# amp_test_filter_route_2.net
KiCad netlist of a schematic drawn in EAGLE
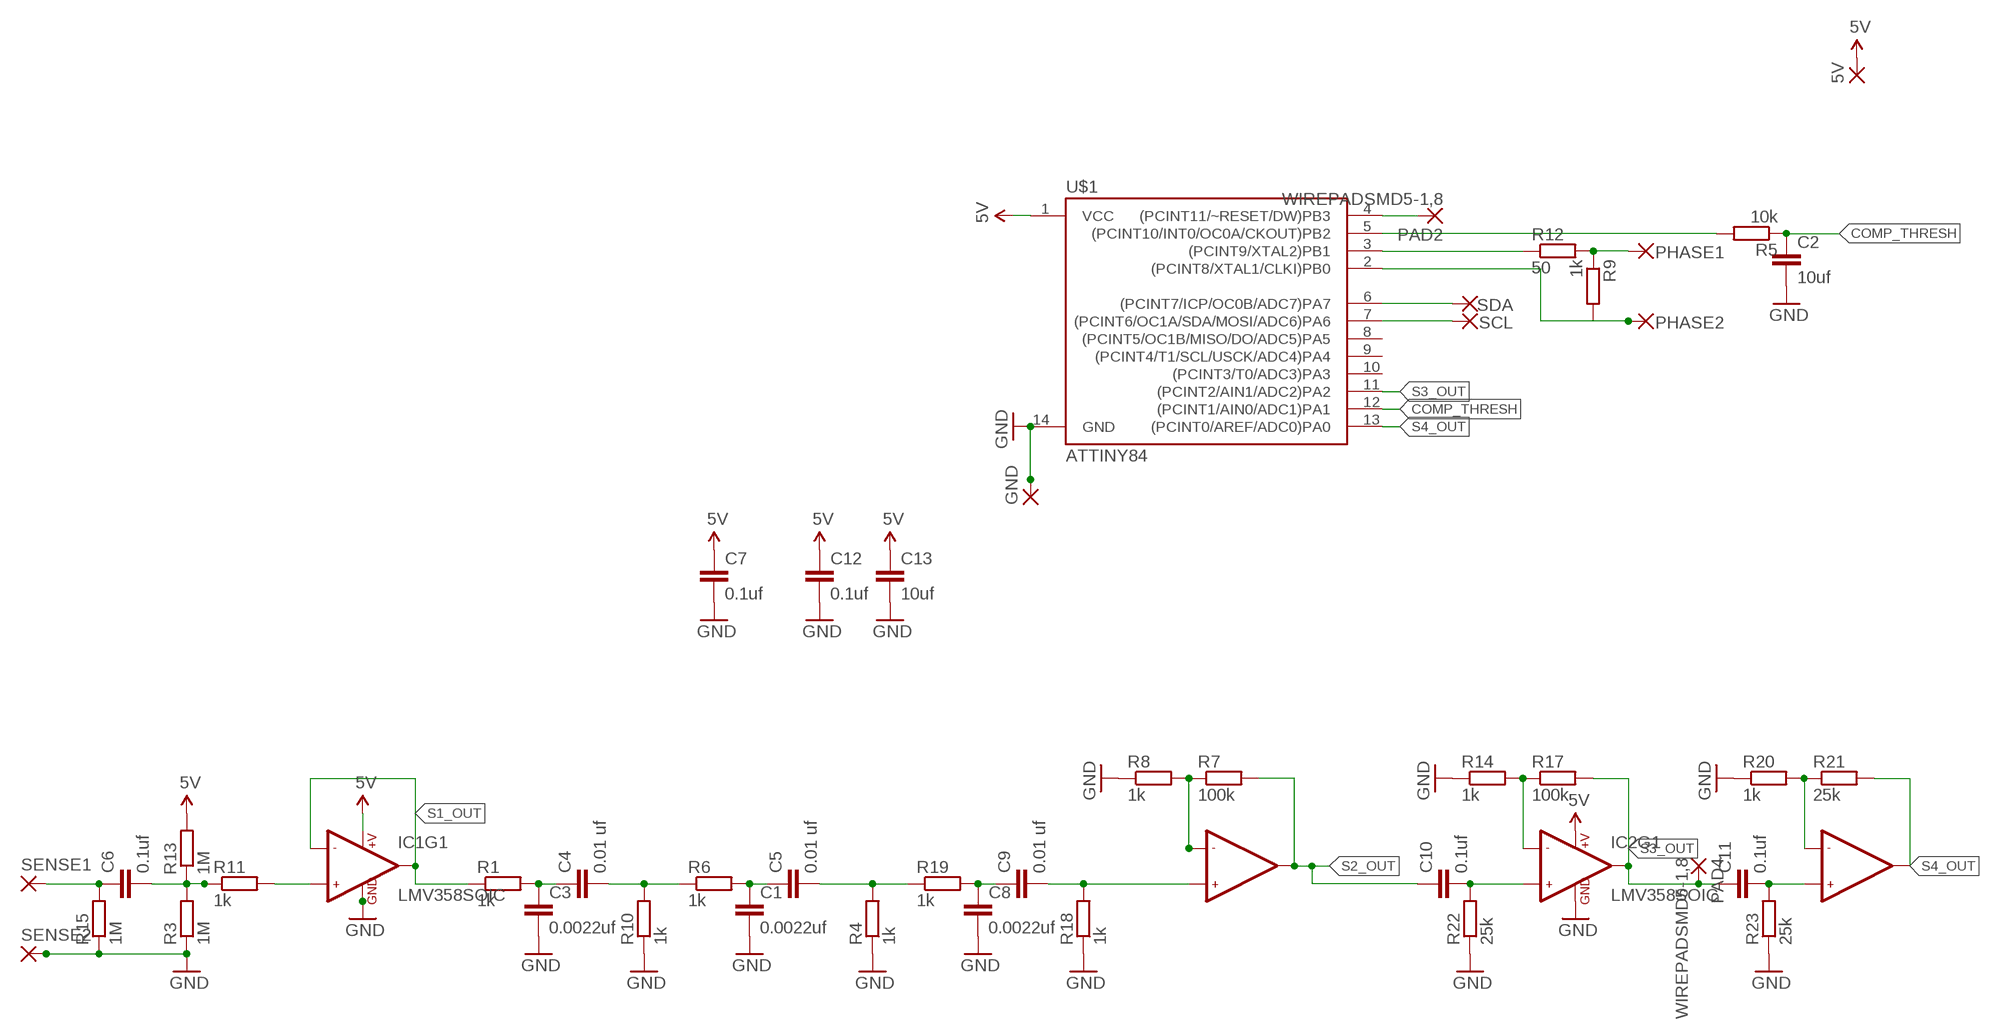
[diagram p0: schematic, sheet 1]

(export (version "E")
  (design (tool "Eeschema 10.0.6"))
  (components
    (comp (ref "5V")
      (value "SMD5")
      (footprint "eagle-import:SMD2,54-5,08")
      (libsource (lib "eagle-import") (part "SMD5"))
    )
    (comp (ref "C1")
      (value "0.0022uf")
      (footprint "eagle-import:C0603")
      (libsource (lib "eagle-import") (part "C-EUC0603"))
    )
    (comp (ref "C2")
      (value "10uf")
      (footprint "eagle-import:C0603")
      (libsource (lib "eagle-import") (part "C-EUC0603"))
    )
    (comp (ref "C3")
      (value "0.0022uf")
      (footprint "eagle-import:C0603")
      (libsource (lib "eagle-import") (part "C-EUC0603"))
    )
    (comp (ref "C4")
      (value "0.01 uf")
      (footprint "eagle-import:C0603")
      (libsource (lib "eagle-import") (part "C-EUC0603"))
    )
    (comp (ref "C5")
      (value "0.01 uf")
      (footprint "eagle-import:C0603")
      (libsource (lib "eagle-import") (part "C-EUC0603"))
    )
    (comp (ref "C6")
      (value "0.1uf")
      (footprint "eagle-import:C0603")
      (libsource (lib "eagle-import") (part "C-EUC0603"))
    )
    (comp (ref "C7")
      (value "0.1uf")
      (footprint "eagle-import:C0603")
      (libsource (lib "eagle-import") (part "C-EUC0603"))
    )
    (comp (ref "C8")
      (value "0.0022uf")
      (footprint "eagle-import:C0603")
      (libsource (lib "eagle-import") (part "C-EUC0603"))
    )
    (comp (ref "C9")
      (value "0.01 uf")
      (footprint "eagle-import:C0603")
      (libsource (lib "eagle-import") (part "C-EUC0603"))
    )
    (comp (ref "C10")
      (value "0.1uf")
      (footprint "eagle-import:C0603")
      (libsource (lib "eagle-import") (part "C-EUC0603"))
    )
    (comp (ref "C11")
      (value "0.1uf")
      (footprint "eagle-import:C0603")
      (libsource (lib "eagle-import") (part "C-EUC0603"))
    )
    (comp (ref "C12")
      (value "0.1uf")
      (footprint "eagle-import:C0603")
      (libsource (lib "eagle-import") (part "C-EUC0603"))
    )
    (comp (ref "C13")
      (value "10uf")
      (footprint "eagle-import:C0603")
      (libsource (lib "eagle-import") (part "C-EUC0603"))
    )
    (comp (ref "GND")
      (value "SMD5")
      (footprint "eagle-import:SMD2,54-5,08")
      (libsource (lib "eagle-import") (part "SMD5"))
    )
    (comp (ref "IC1")
      (value "LMV358SOIC")
      (footprint "eagle-import:SO08")
      (libsource (lib "eagle-import") (part "LMV358SOIC"))
    )
    (comp (ref "IC2")
      (value "LMV358SOIC")
      (footprint "eagle-import:SO08")
      (libsource (lib "eagle-import") (part "LMV358SOIC"))
    )
    (comp (ref "PAD2")
      (value "WIREPADSMD5-1,8")
      (footprint "eagle-import:5-1,8")
      (libsource (lib "eagle-import") (part "WIREPADSMD5-1,8"))
    )
    (comp (ref "PAD4")
      (value "WIREPADSMD5-1,8")
      (footprint "eagle-import:5-1,8")
      (libsource (lib "eagle-import") (part "WIREPADSMD5-1,8"))
    )
    (comp (ref "PHASE1")
      (value "SMD5")
      (footprint "eagle-import:SMD2,54-5,08")
      (libsource (lib "eagle-import") (part "SMD5"))
    )
    (comp (ref "PHASE2")
      (value "SMD5")
      (footprint "eagle-import:SMD2,54-5,08")
      (libsource (lib "eagle-import") (part "SMD5"))
    )
    (comp (ref "R1")
      (value "1k")
      (footprint "eagle-import:R0603")
      (libsource (lib "eagle-import") (part "R-EU_R0603"))
    )
    (comp (ref "R3")
      (value "1M")
      (footprint "eagle-import:R0603")
      (libsource (lib "eagle-import") (part "R-EU_R0603"))
    )
    (comp (ref "R4")
      (value "1k")
      (footprint "eagle-import:R0603")
      (libsource (lib "eagle-import") (part "R-EU_R0603"))
    )
    (comp (ref "R5")
      (value "10k")
      (footprint "eagle-import:R0603")
      (libsource (lib "eagle-import") (part "R-EU_R0603"))
    )
    (comp (ref "R6")
      (value "1k")
      (footprint "eagle-import:R0603")
      (libsource (lib "eagle-import") (part "R-EU_R0603"))
    )
    (comp (ref "R7")
      (value "100k")
      (footprint "eagle-import:R0603")
      (libsource (lib "eagle-import") (part "R-EU_R0603"))
    )
    (comp (ref "R8")
      (value "1k")
      (footprint "eagle-import:R0603")
      (libsource (lib "eagle-import") (part "R-EU_R0603"))
    )
    (comp (ref "R9")
      (value "1k")
      (footprint "eagle-import:R0603")
      (libsource (lib "eagle-import") (part "R-EU_R0603"))
    )
    (comp (ref "R10")
      (value "1k")
      (footprint "eagle-import:R0603")
      (libsource (lib "eagle-import") (part "R-EU_R0603"))
    )
    (comp (ref "R11")
      (value "1k")
      (footprint "eagle-import:R0603")
      (libsource (lib "eagle-import") (part "R-EU_R0603"))
    )
    (comp (ref "R12")
      (value "50")
      (footprint "eagle-import:R0603")
      (libsource (lib "eagle-import") (part "R-EU_R0603"))
    )
    (comp (ref "R13")
      (value "1M")
      (footprint "eagle-import:R0603")
      (libsource (lib "eagle-import") (part "R-EU_R0603"))
    )
    (comp (ref "R14")
      (value "1k")
      (footprint "eagle-import:R0603")
      (libsource (lib "eagle-import") (part "R-EU_R0603"))
    )
    (comp (ref "R15")
      (value "1M")
      (footprint "eagle-import:R0603")
      (libsource (lib "eagle-import") (part "R-EU_R0603"))
    )
    (comp (ref "R17")
      (value "100k")
      (footprint "eagle-import:R0603")
      (libsource (lib "eagle-import") (part "R-EU_R0603"))
    )
    (comp (ref "R18")
      (value "1k")
      (footprint "eagle-import:R0603")
      (libsource (lib "eagle-import") (part "R-EU_R0603"))
    )
    (comp (ref "R19")
      (value "1k")
      (footprint "eagle-import:R0603")
      (libsource (lib "eagle-import") (part "R-EU_R0603"))
    )
    (comp (ref "R20")
      (value "1k")
      (footprint "eagle-import:R0603")
      (libsource (lib "eagle-import") (part "R-EU_R0603"))
    )
    (comp (ref "R21")
      (value "25k")
      (footprint "eagle-import:R0603")
      (libsource (lib "eagle-import") (part "R-EU_R0603"))
    )
    (comp (ref "R22")
      (value "25k")
      (footprint "eagle-import:R0603")
      (libsource (lib "eagle-import") (part "R-EU_R0603"))
    )
    (comp (ref "R23")
      (value "25k")
      (footprint "eagle-import:R0603")
      (libsource (lib "eagle-import") (part "R-EU_R0603"))
    )
    (comp (ref "SCL")
      (value "SMD5")
      (footprint "eagle-import:SMD2,54-5,08")
      (libsource (lib "eagle-import") (part "SMD5"))
    )
    (comp (ref "SDA")
      (value "SMD5")
      (footprint "eagle-import:SMD2,54-5,08")
      (libsource (lib "eagle-import") (part "SMD5"))
    )
    (comp (ref "SENSE1")
      (value "SMD5")
      (footprint "eagle-import:SMD2,54-5,08")
      (libsource (lib "eagle-import") (part "SMD5"))
    )
    (comp (ref "SENSE2")
      (value "SMD5")
      (footprint "eagle-import:SMD2,54-5,08")
      (libsource (lib "eagle-import") (part "SMD5"))
    )
    (comp (ref "U$1")
      (value "ATTINY84")
      (footprint "eagle-import:SO14")
      (libsource (lib "eagle-import") (part "ATTINY84"))
    )
  )
  (nets
    (net (code "1") (name "5V") (class "Default")
      (node (ref "5V") (pin "1") (pinfunction "P_1") (pintype "passive"))
      (node (ref "C12") (pin "1") (pinfunction "1_1") (pintype "passive"))
      (node (ref "C13") (pin "1") (pinfunction "1_1") (pintype "passive"))
      (node (ref "C7") (pin "1") (pinfunction "1_1") (pintype "passive"))
      (node (ref "IC1") (pin "8") (pinfunction "+V_8") (pintype "power_in"))
      (node (ref "IC2") (pin "8") (pinfunction "+V_8") (pintype "power_in"))
      (node (ref "R13") (pin "2") (pinfunction "2_2") (pintype "passive"))
      (node (ref "U$1") (pin "1") (pinfunction "VCC_1") (pintype "bidirectional"))
    )
    (net (code "2") (name "COMP_THRESH") (class "Default")
      (node (ref "C2") (pin "1") (pinfunction "1_1") (pintype "passive"))
      (node (ref "R5") (pin "1") (pinfunction "1_1") (pintype "passive"))
      (node (ref "U$1") (pin "12") (pinfunction "(PCINT1/AIN0/ADC1)PA1_12") (pintype "bidirectional"))
    )
    (net (code "3") (name "GND") (class "Default")
      (node (ref "C1") (pin "2") (pinfunction "2_2") (pintype "passive"))
      (node (ref "C12") (pin "2") (pinfunction "2_2") (pintype "passive"))
      (node (ref "C13") (pin "2") (pinfunction "2_2") (pintype "passive"))
      (node (ref "C2") (pin "2") (pinfunction "2_2") (pintype "passive"))
      (node (ref "C3") (pin "2") (pinfunction "2_2") (pintype "passive"))
      (node (ref "C7") (pin "2") (pinfunction "2_2") (pintype "passive"))
      (node (ref "C8") (pin "2") (pinfunction "2_2") (pintype "passive"))
      (node (ref "GND") (pin "1") (pinfunction "P_1") (pintype "passive"))
      (node (ref "IC1") (pin "4") (pinfunction "GND_4") (pintype "power_in"))
      (node (ref "IC2") (pin "4") (pinfunction "GND_4") (pintype "power_in"))
      (node (ref "R10") (pin "1") (pinfunction "1_1") (pintype "passive"))
      (node (ref "R14") (pin "1") (pinfunction "1_1") (pintype "passive"))
      (node (ref "R15") (pin "1") (pinfunction "1_1") (pintype "passive"))
      (node (ref "R18") (pin "1") (pinfunction "1_1") (pintype "passive"))
      (node (ref "R20") (pin "1") (pinfunction "1_1") (pintype "passive"))
      (node (ref "R22") (pin "1") (pinfunction "1_1") (pintype "passive"))
      (node (ref "R23") (pin "1") (pinfunction "1_1") (pintype "passive"))
      (node (ref "R3") (pin "1") (pinfunction "1_1") (pintype "passive"))
      (node (ref "R4") (pin "1") (pinfunction "1_1") (pintype "passive"))
      (node (ref "R8") (pin "1") (pinfunction "1_1") (pintype "passive"))
      (node (ref "SENSE2") (pin "1") (pinfunction "P_1") (pintype "passive"))
      (node (ref "U$1") (pin "14") (pinfunction "GND_14") (pintype "bidirectional"))
    )
    (net (code "4") (name "Net-(C1-Pad1)") (class "Default")
      (node (ref "C1") (pin "1") (pinfunction "1_1") (pintype "passive"))
      (node (ref "C5") (pin "1") (pinfunction "1_1") (pintype "passive"))
      (node (ref "R6") (pin "2") (pinfunction "2_2") (pintype "passive"))
    )
    (net (code "5") (name "Net-(C3-Pad1)") (class "Default")
      (node (ref "C3") (pin "1") (pinfunction "1_1") (pintype "passive"))
      (node (ref "C4") (pin "1") (pinfunction "1_1") (pintype "passive"))
      (node (ref "R1") (pin "2") (pinfunction "2_2") (pintype "passive"))
    )
    (net (code "6") (name "Net-(C4-Pad2)") (class "Default")
      (node (ref "C4") (pin "2") (pinfunction "2_2") (pintype "passive"))
      (node (ref "R10") (pin "2") (pinfunction "2_2") (pintype "passive"))
      (node (ref "R6") (pin "1") (pinfunction "1_1") (pintype "passive"))
    )
    (net (code "7") (name "Net-(C5-Pad2)") (class "Default")
      (node (ref "C5") (pin "2") (pinfunction "2_2") (pintype "passive"))
      (node (ref "R19") (pin "1") (pinfunction "1_1") (pintype "passive"))
      (node (ref "R4") (pin "2") (pinfunction "2_2") (pintype "passive"))
    )
    (net (code "8") (name "Net-(C6-Pad2)") (class "Default")
      (node (ref "C6") (pin "2") (pinfunction "2_2") (pintype "passive"))
      (node (ref "R11") (pin "1") (pinfunction "1_1") (pintype "passive"))
      (node (ref "R13") (pin "1") (pinfunction "1_1") (pintype "passive"))
      (node (ref "R3") (pin "2") (pinfunction "2_2") (pintype "passive"))
    )
    (net (code "9") (name "Net-(C8-Pad1)") (class "Default")
      (node (ref "C8") (pin "1") (pinfunction "1_1") (pintype "passive"))
      (node (ref "C9") (pin "1") (pinfunction "1_1") (pintype "passive"))
      (node (ref "R19") (pin "2") (pinfunction "2_2") (pintype "passive"))
    )
    (net (code "10") (name "Net-(IC1A-+IN1)") (class "Default")
      (node (ref "IC1") (pin "3") (pinfunction "+IN1_3") (pintype "input"))
      (node (ref "R11") (pin "2") (pinfunction "2_2") (pintype "passive"))
    )
    (net (code "11") (name "Net-(IC1B-+IN2)") (class "Default")
      (node (ref "C9") (pin "2") (pinfunction "2_2") (pintype "passive"))
      (node (ref "IC1") (pin "5") (pinfunction "+IN2_5") (pintype "input"))
      (node (ref "R18") (pin "2") (pinfunction "2_2") (pintype "passive"))
    )
    (net (code "12") (name "Net-(IC1B--IN2)") (class "Default")
      (node (ref "IC1") (pin "6") (pinfunction "-IN2_6") (pintype "input"))
      (node (ref "R7") (pin "1") (pinfunction "1_1") (pintype "passive"))
      (node (ref "R8") (pin "2") (pinfunction "2_2") (pintype "passive"))
    )
    (net (code "13") (name "Net-(IC2A-+IN1)") (class "Default")
      (node (ref "C10") (pin "2") (pinfunction "2_2") (pintype "passive"))
      (node (ref "IC2") (pin "3") (pinfunction "+IN1_3") (pintype "input"))
      (node (ref "R22") (pin "2") (pinfunction "2_2") (pintype "passive"))
    )
    (net (code "14") (name "Net-(IC2A--IN1)") (class "Default")
      (node (ref "IC2") (pin "2") (pinfunction "-IN1_2") (pintype "input"))
      (node (ref "R14") (pin "2") (pinfunction "2_2") (pintype "passive"))
      (node (ref "R17") (pin "1") (pinfunction "1_1") (pintype "passive"))
    )
    (net (code "15") (name "Net-(IC2B-+IN2)") (class "Default")
      (node (ref "C11") (pin "2") (pinfunction "2_2") (pintype "passive"))
      (node (ref "IC2") (pin "5") (pinfunction "+IN2_5") (pintype "input"))
      (node (ref "R23") (pin "2") (pinfunction "2_2") (pintype "passive"))
    )
    (net (code "16") (name "Net-(IC2B--IN2)") (class "Default")
      (node (ref "IC2") (pin "6") (pinfunction "-IN2_6") (pintype "input"))
      (node (ref "R20") (pin "2") (pinfunction "2_2") (pintype "passive"))
      (node (ref "R21") (pin "1") (pinfunction "1_1") (pintype "passive"))
    )
    (net (code "17") (name "Net-(PAD2-P)") (class "Default")
      (node (ref "PAD2") (pin "1") (pinfunction "P_1") (pintype "passive"))
      (node (ref "U$1") (pin "4") (pinfunction "(PCINT11/~{RESET/DW})PB3_4") (pintype "bidirectional"))
    )
    (net (code "18") (name "Net-(PHASE1-P)") (class "Default")
      (node (ref "PHASE1") (pin "1") (pinfunction "P_1") (pintype "passive"))
      (node (ref "R12") (pin "2") (pinfunction "2_2") (pintype "passive"))
      (node (ref "R9") (pin "1") (pinfunction "1_1") (pintype "passive"))
    )
    (net (code "19") (name "Net-(PHASE2-P)") (class "Default")
      (node (ref "PHASE2") (pin "1") (pinfunction "P_1") (pintype "passive"))
      (node (ref "R9") (pin "2") (pinfunction "2_2") (pintype "passive"))
      (node (ref "U$1") (pin "2") (pinfunction "(PCINT8/XTAL1/CLKI)PB0_2") (pintype "bidirectional"))
    )
    (net (code "20") (name "Net-(SCL-P)") (class "Default")
      (node (ref "SCL") (pin "1") (pinfunction "P_1") (pintype "passive"))
      (node (ref "U$1") (pin "7") (pinfunction "(PCINT6/OC1A/SDA/MOSI/ADC6)PA6_7") (pintype "bidirectional"))
    )
    (net (code "21") (name "Net-(SDA-P)") (class "Default")
      (node (ref "SDA") (pin "1") (pinfunction "P_1") (pintype "passive"))
      (node (ref "U$1") (pin "6") (pinfunction "(PCINT7/ICP/OC0B/ADC7)PA7_6") (pintype "bidirectional"))
    )
    (net (code "22") (name "Net-(SENSE1-P)") (class "Default")
      (node (ref "C6") (pin "1") (pinfunction "1_1") (pintype "passive"))
      (node (ref "R15") (pin "2") (pinfunction "2_2") (pintype "passive"))
      (node (ref "SENSE1") (pin "1") (pinfunction "P_1") (pintype "passive"))
    )
    (net (code "23") (name "Net-(U$1-(PCINT9{slash}XTAL2)PB1)") (class "Default")
      (node (ref "R12") (pin "1") (pinfunction "1_1") (pintype "passive"))
      (node (ref "U$1") (pin "3") (pinfunction "(PCINT9/XTAL2)PB1_3") (pintype "bidirectional"))
    )
    (net (code "24") (name "Net-(U$1-(PCINT10{slash}INT0{slash}OC0A{slash}CKOUT)PB2)") (class "Default")
      (node (ref "R5") (pin "2") (pinfunction "2_2") (pintype "passive"))
      (node (ref "U$1") (pin "5") (pinfunction "(PCINT10/INT0/OC0A/CKOUT)PB2_5") (pintype "bidirectional"))
    )
    (net (code "25") (name "S1_OUT") (class "Default")
      (node (ref "IC1") (pin "1") (pinfunction "OUT1_1") (pintype "output"))
      (node (ref "IC1") (pin "2") (pinfunction "-IN1_2") (pintype "input"))
      (node (ref "R1") (pin "1") (pinfunction "1_1") (pintype "passive"))
    )
    (net (code "26") (name "S2_OUT") (class "Default")
      (node (ref "C10") (pin "1") (pinfunction "1_1") (pintype "passive"))
      (node (ref "IC1") (pin "7") (pinfunction "OUT2_7") (pintype "output"))
      (node (ref "R7") (pin "2") (pinfunction "2_2") (pintype "passive"))
    )
    (net (code "27") (name "S3_OUT") (class "Default")
      (node (ref "C11") (pin "1") (pinfunction "1_1") (pintype "passive"))
      (node (ref "IC2") (pin "1") (pinfunction "OUT1_1") (pintype "output"))
      (node (ref "PAD4") (pin "1") (pinfunction "P_1") (pintype "passive"))
      (node (ref "R17") (pin "2") (pinfunction "2_2") (pintype "passive"))
      (node (ref "U$1") (pin "11") (pinfunction "(PCINT2/AIN1/ADC2)PA2_11") (pintype "bidirectional"))
    )
    (net (code "28") (name "S4_OUT") (class "Default")
      (node (ref "IC2") (pin "7") (pinfunction "OUT2_7") (pintype "output"))
      (node (ref "R21") (pin "2") (pinfunction "2_2") (pintype "passive"))
      (node (ref "U$1") (pin "13") (pinfunction "(PCINT0/AREF/ADC0)PA0_13") (pintype "bidirectional"))
    )
    (net (code "29") (name "unconnected-(U$1-(PCINT3{slash}T0{slash}ADC3)PA3-Pad10)") (class "Default")
      (node (ref "U$1") (pin "10") (pinfunction "(PCINT3/T0/ADC3)PA3_10") (pintype "bidirectional"))
    )
    (net (code "30") (name "unconnected-(U$1-(PCINT4{slash}T1{slash}SCL{slash}USCK{slash}ADC4)PA4-Pad9)") (class "Default")
      (node (ref "U$1") (pin "9") (pinfunction "(PCINT4/T1/SCL/USCK/ADC4)PA4_9") (pintype "bidirectional"))
    )
    (net (code "31") (name "unconnected-(U$1-(PCINT5{slash}OC1B{slash}MISO{slash}DO{slash}ADC5)PA5-Pad8)") (class "Default")
      (node (ref "U$1") (pin "8") (pinfunction "(PCINT5/OC1B/MISO/DO/ADC5)PA5_8") (pintype "bidirectional"))
    )
  )
)
